# Sheet8.net
KiCad netlist of a schematic drawn in Altium Designer
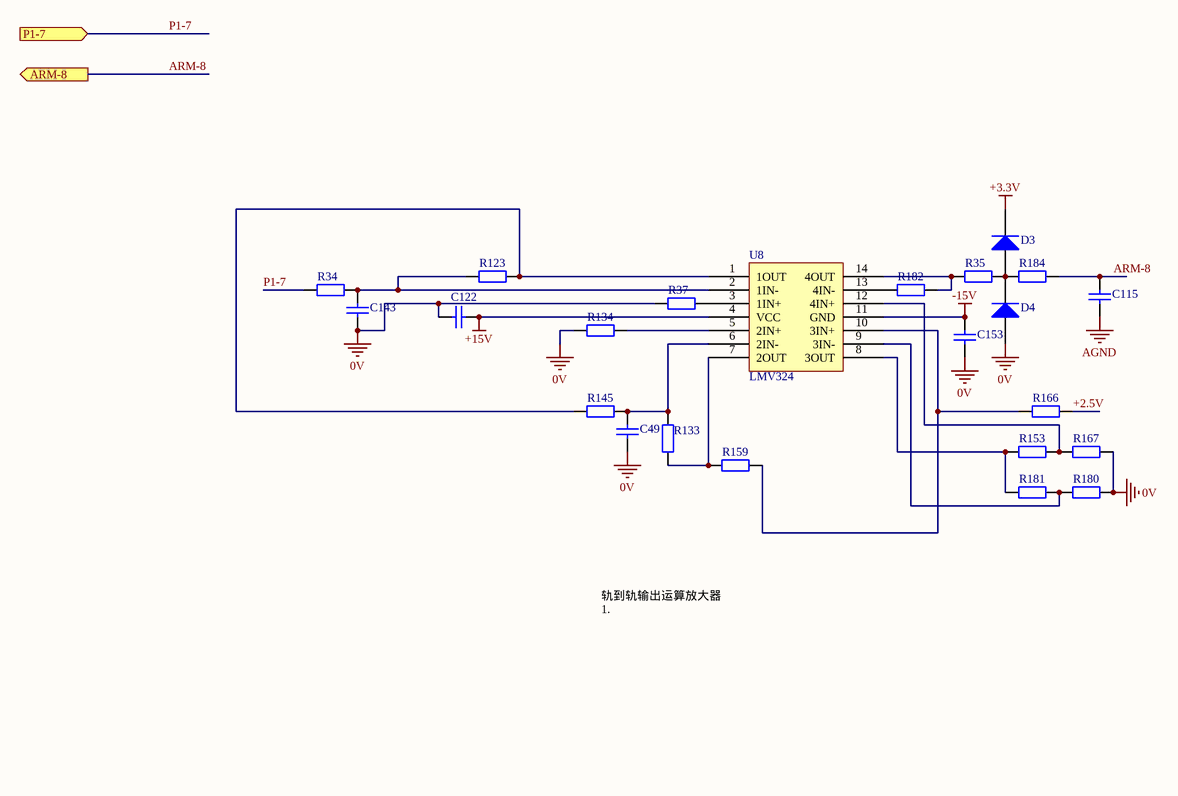
[diagram p0: Sheet8.SchDoc]

(export (version "E")
  (design (tool "Eeschema 10.0.6"))
  (components
    (comp (ref "C49")
      (value "Cap")
      (footprint "RAD-0.3")
      (description "Capacitor")
      (fields (field (name "PUBLISHER") "Altium Limited"))
      (libsource (lib "Miscellaneous Devices") (part "Cap"))
    )
    (comp (ref "C115")
      (value "Cap")
      (footprint "RAD-0.3")
      (description "Capacitor")
      (fields (field (name "PUBLISHER") "Altium Limited"))
      (libsource (lib "Miscellaneous Devices") (part "Cap"))
    )
    (comp (ref "C122")
      (value "Cap")
      (footprint "RAD-0.3")
      (description "Capacitor")
      (fields (field (name "PUBLISHER") "Altium Limited"))
      (libsource (lib "Miscellaneous Devices") (part "Cap"))
    )
    (comp (ref "C143")
      (value "Cap")
      (footprint "RAD-0.3")
      (description "Capacitor")
      (fields (field (name "PUBLISHER") "Altium Limited"))
      (libsource (lib "Miscellaneous Devices") (part "Cap"))
    )
    (comp (ref "C153")
      (value "Cap")
      (footprint "RAD-0.3")
      (description "Capacitor")
      (fields (field (name "PUBLISHER") "Altium Limited"))
      (libsource (lib "Miscellaneous Devices") (part "Cap"))
    )
    (comp (ref "D3")
      (value "Diode 1N4007")
      (footprint "DO-41")
      (description "1 Amp General Purpose Rectifier")
      (fields (field (name "PUBLISHER") "Altium Limited"))
      (libsource (lib "Miscellaneous Devices") (part "Diode 1N4007"))
    )
    (comp (ref "D4")
      (value "Diode 1N4007")
      (footprint "DO-41")
      (description "1 Amp General Purpose Rectifier")
      (fields (field (name "PUBLISHER") "Altium Limited"))
      (libsource (lib "Miscellaneous Devices") (part "Diode 1N4007"))
    )
    (comp (ref "R34")
      (value "Res2")
      (footprint "AXIAL-0.4")
      (description "Resistor")
      (fields (field (name "PUBLISHER") "Altium Limited"))
      (libsource (lib "Miscellaneous Devices") (part "Res2"))
    )
    (comp (ref "R35")
      (value "Res2")
      (footprint "AXIAL-0.4")
      (description "Resistor")
      (fields (field (name "PUBLISHER") "Altium Limited"))
      (libsource (lib "") (part "Res2_1"))
    )
    (comp (ref "R37")
      (value "Res2")
      (footprint "AXIAL-0.4")
      (description "Resistor")
      (fields (field (name "PUBLISHER") "Altium Limited"))
      (libsource (lib "Miscellaneous Devices") (part "Res2"))
    )
    (comp (ref "R123")
      (value "Res2")
      (footprint "AXIAL-0.4")
      (description "Resistor")
      (fields (field (name "PUBLISHER") "Altium Limited"))
      (libsource (lib "Miscellaneous Devices") (part "Res2"))
    )
    (comp (ref "R133")
      (value "Res2")
      (footprint "AXIAL-0.4")
      (description "Resistor")
      (fields (field (name "PUBLISHER") "Altium Limited"))
      (libsource (lib "") (part "Res2_2"))
    )
    (comp (ref "R134")
      (value "Res2")
      (footprint "AXIAL-0.4")
      (description "Resistor")
      (fields (field (name "PUBLISHER") "Altium Limited"))
      (libsource (lib "Miscellaneous Devices") (part "Res2"))
    )
    (comp (ref "R145")
      (value "Res2")
      (footprint "AXIAL-0.4")
      (description "Resistor")
      (fields (field (name "PUBLISHER") "Altium Limited"))
      (libsource (lib "Miscellaneous Devices") (part "Res2"))
    )
    (comp (ref "R153")
      (value "Res2")
      (footprint "AXIAL-0.4")
      (description "Resistor")
      (fields (field (name "PUBLISHER") "Altium Limited"))
      (libsource (lib "") (part "Res2_1"))
    )
    (comp (ref "R159")
      (value "Res2")
      (footprint "AXIAL-0.4")
      (description "Resistor")
      (fields (field (name "PUBLISHER") "Altium Limited"))
      (libsource (lib "") (part "Res2_1"))
    )
    (comp (ref "R166")
      (value "Res2")
      (footprint "AXIAL-0.4")
      (description "Resistor")
      (fields (field (name "PUBLISHER") "Altium Limited"))
      (libsource (lib "") (part "Res2_1"))
    )
    (comp (ref "R167")
      (value "Res2")
      (footprint "AXIAL-0.4")
      (description "Resistor")
      (fields (field (name "PUBLISHER") "Altium Limited"))
      (libsource (lib "") (part "Res2_1"))
    )
    (comp (ref "R180")
      (value "Res2")
      (footprint "AXIAL-0.4")
      (description "Resistor")
      (fields (field (name "PUBLISHER") "Altium Limited"))
      (libsource (lib "") (part "Res2_1"))
    )
    (comp (ref "R181")
      (value "Res2")
      (footprint "AXIAL-0.4")
      (description "Resistor")
      (fields (field (name "PUBLISHER") "Altium Limited"))
      (libsource (lib "") (part "Res2_1"))
    )
    (comp (ref "R182")
      (value "Res2")
      (footprint "AXIAL-0.4")
      (description "Resistor")
      (fields (field (name "PUBLISHER") "Altium Limited"))
      (libsource (lib "") (part "Res2_1"))
    )
    (comp (ref "R184")
      (value "Res2")
      (footprint "AXIAL-0.4")
      (description "Resistor")
      (fields (field (name "PUBLISHER") "Altium Limited"))
      (libsource (lib "") (part "Res2_1"))
    )
    (comp (ref "U8") (value "LMV324") (libsource (lib "LMV324") (part "Component_1")))
  )
  (nets
    (net (code "1") (name "+3.3V") (class "Default")
      (node (ref "D3") (pin "2") (pinfunction "K_2") (pintype "passive"))
    )
    (net (code "2") (name "+15V") (class "Default")
      (node (ref "C122") (pin "1") (pinfunction "1_1") (pintype "passive"))
      (node (ref "U8") (pin "4") (pinfunction "VCC_4") (pintype "passive"))
    )
    (net (code "3") (name "-15V") (class "Default")
      (node (ref "C153") (pin "2") (pinfunction "2_2") (pintype "passive"))
      (node (ref "U8") (pin "11") (pinfunction "GND_11") (pintype "passive"))
    )
    (net (code "4") (name "/+2.5V") (class "Default")
      (node (ref "R166") (pin "2") (pinfunction "2_2") (pintype "passive"))
    )
    (net (code "5") (name "/ARM-8") (class "Default")
      (node (ref "C115") (pin "2") (pinfunction "2_2") (pintype "passive"))
      (node (ref "R184") (pin "2") (pinfunction "2_2") (pintype "passive"))
    )
    (net (code "6") (name "/P1-7") (class "Default")
      (node (ref "R34") (pin "2") (pinfunction "2_2") (pintype "passive"))
    )
    (net (code "7") (name "0V") (class "Default")
      (node (ref "C122") (pin "2") (pinfunction "2_2") (pintype "passive"))
      (node (ref "C143") (pin "1") (pinfunction "1_1") (pintype "passive"))
      (node (ref "C153") (pin "1") (pinfunction "1_1") (pintype "passive"))
      (node (ref "C49") (pin "1") (pinfunction "1_1") (pintype "passive"))
      (node (ref "D4") (pin "1") (pinfunction "A_1") (pintype "passive"))
      (node (ref "R134") (pin "2") (pinfunction "2_2") (pintype "passive"))
      (node (ref "R167") (pin "2") (pinfunction "2_2") (pintype "passive"))
      (node (ref "R180") (pin "2") (pinfunction "2_2") (pintype "passive"))
      (node (ref "R37") (pin "2") (pinfunction "2_2") (pintype "passive"))
    )
    (net (code "8") (name "AGND") (class "Default")
      (node (ref "C115") (pin "1") (pinfunction "1_1") (pintype "passive"))
    )
    (net (code "9") (name "Net-(D3-A)") (class "Default")
      (node (ref "D3") (pin "1") (pinfunction "A_1") (pintype "passive"))
      (node (ref "D4") (pin "2") (pinfunction "K_2") (pintype "passive"))
      (node (ref "R184") (pin "1") (pinfunction "1_1") (pintype "passive"))
      (node (ref "R35") (pin "2") (pinfunction "2_2") (pintype "passive"))
    )
    (net (code "10") (name "Net-(U8-1IN+)") (class "Default")
      (node (ref "R37") (pin "1") (pinfunction "1_1") (pintype "passive"))
      (node (ref "U8") (pin "3") (pinfunction "1IN+_3") (pintype "passive"))
    )
    (net (code "11") (name "Net-(U8-1IN-)") (class "Default")
      (node (ref "C143") (pin "2") (pinfunction "2_2") (pintype "passive"))
      (node (ref "R123") (pin "2") (pinfunction "2_2") (pintype "passive"))
      (node (ref "R34") (pin "1") (pinfunction "1_1") (pintype "passive"))
      (node (ref "U8") (pin "2") (pinfunction "1IN-_2") (pintype "passive"))
    )
    (net (code "12") (name "Net-(U8-1OUT)") (class "Default")
      (node (ref "R123") (pin "1") (pinfunction "1_1") (pintype "passive"))
      (node (ref "R145") (pin "2") (pinfunction "2_2") (pintype "passive"))
      (node (ref "U8") (pin "1") (pinfunction "1OUT_1") (pintype "passive"))
    )
    (net (code "13") (name "Net-(U8-2IN+)") (class "Default")
      (node (ref "R134") (pin "1") (pinfunction "1_1") (pintype "passive"))
      (node (ref "U8") (pin "5") (pinfunction "2IN+_5") (pintype "passive"))
    )
    (net (code "14") (name "Net-(U8-2IN-)") (class "Default")
      (node (ref "C49") (pin "2") (pinfunction "2_2") (pintype "passive"))
      (node (ref "R133") (pin "2") (pinfunction "2_2") (pintype "passive"))
      (node (ref "R145") (pin "1") (pinfunction "1_1") (pintype "passive"))
      (node (ref "U8") (pin "6") (pinfunction "2IN-_6") (pintype "passive"))
    )
    (net (code "15") (name "Net-(U8-2OUT)") (class "Default")
      (node (ref "R133") (pin "1") (pinfunction "1_1") (pintype "passive"))
      (node (ref "R159") (pin "1") (pinfunction "1_1") (pintype "passive"))
      (node (ref "U8") (pin "7") (pinfunction "2OUT_7") (pintype "passive"))
    )
    (net (code "16") (name "Net-(U8-3IN+)") (class "Default")
      (node (ref "R159") (pin "2") (pinfunction "2_2") (pintype "passive"))
      (node (ref "R166") (pin "1") (pinfunction "1_1") (pintype "passive"))
      (node (ref "U8") (pin "10") (pinfunction "3IN+_10") (pintype "passive"))
    )
    (net (code "17") (name "Net-(U8-3IN-)") (class "Default")
      (node (ref "R180") (pin "1") (pinfunction "1_1") (pintype "passive"))
      (node (ref "R181") (pin "2") (pinfunction "2_2") (pintype "passive"))
      (node (ref "U8") (pin "9") (pinfunction "3IN-_9") (pintype "passive"))
    )
    (net (code "18") (name "Net-(U8-3OUT)") (class "Default")
      (node (ref "R153") (pin "1") (pinfunction "1_1") (pintype "passive"))
      (node (ref "R181") (pin "1") (pinfunction "1_1") (pintype "passive"))
      (node (ref "U8") (pin "8") (pinfunction "3OUT_8") (pintype "passive"))
    )
    (net (code "19") (name "Net-(U8-4IN+)") (class "Default")
      (node (ref "R153") (pin "2") (pinfunction "2_2") (pintype "passive"))
      (node (ref "R167") (pin "1") (pinfunction "1_1") (pintype "passive"))
      (node (ref "U8") (pin "12") (pinfunction "4IN+_12") (pintype "passive"))
    )
    (net (code "20") (name "Net-(U8-4IN-)") (class "Default")
      (node (ref "R182") (pin "1") (pinfunction "1_1") (pintype "passive"))
      (node (ref "U8") (pin "13") (pinfunction "4IN-_13") (pintype "passive"))
    )
    (net (code "21") (name "Net-(U8-4OUT)") (class "Default")
      (node (ref "R182") (pin "2") (pinfunction "2_2") (pintype "passive"))
      (node (ref "R35") (pin "1") (pinfunction "1_1") (pintype "passive"))
      (node (ref "U8") (pin "14") (pinfunction "4OUT_14") (pintype "passive"))
    )
  )
)
